# FK723MK1_ZGT6_Large.net
KiCad netlist of a schematic drawn in Altium Designer
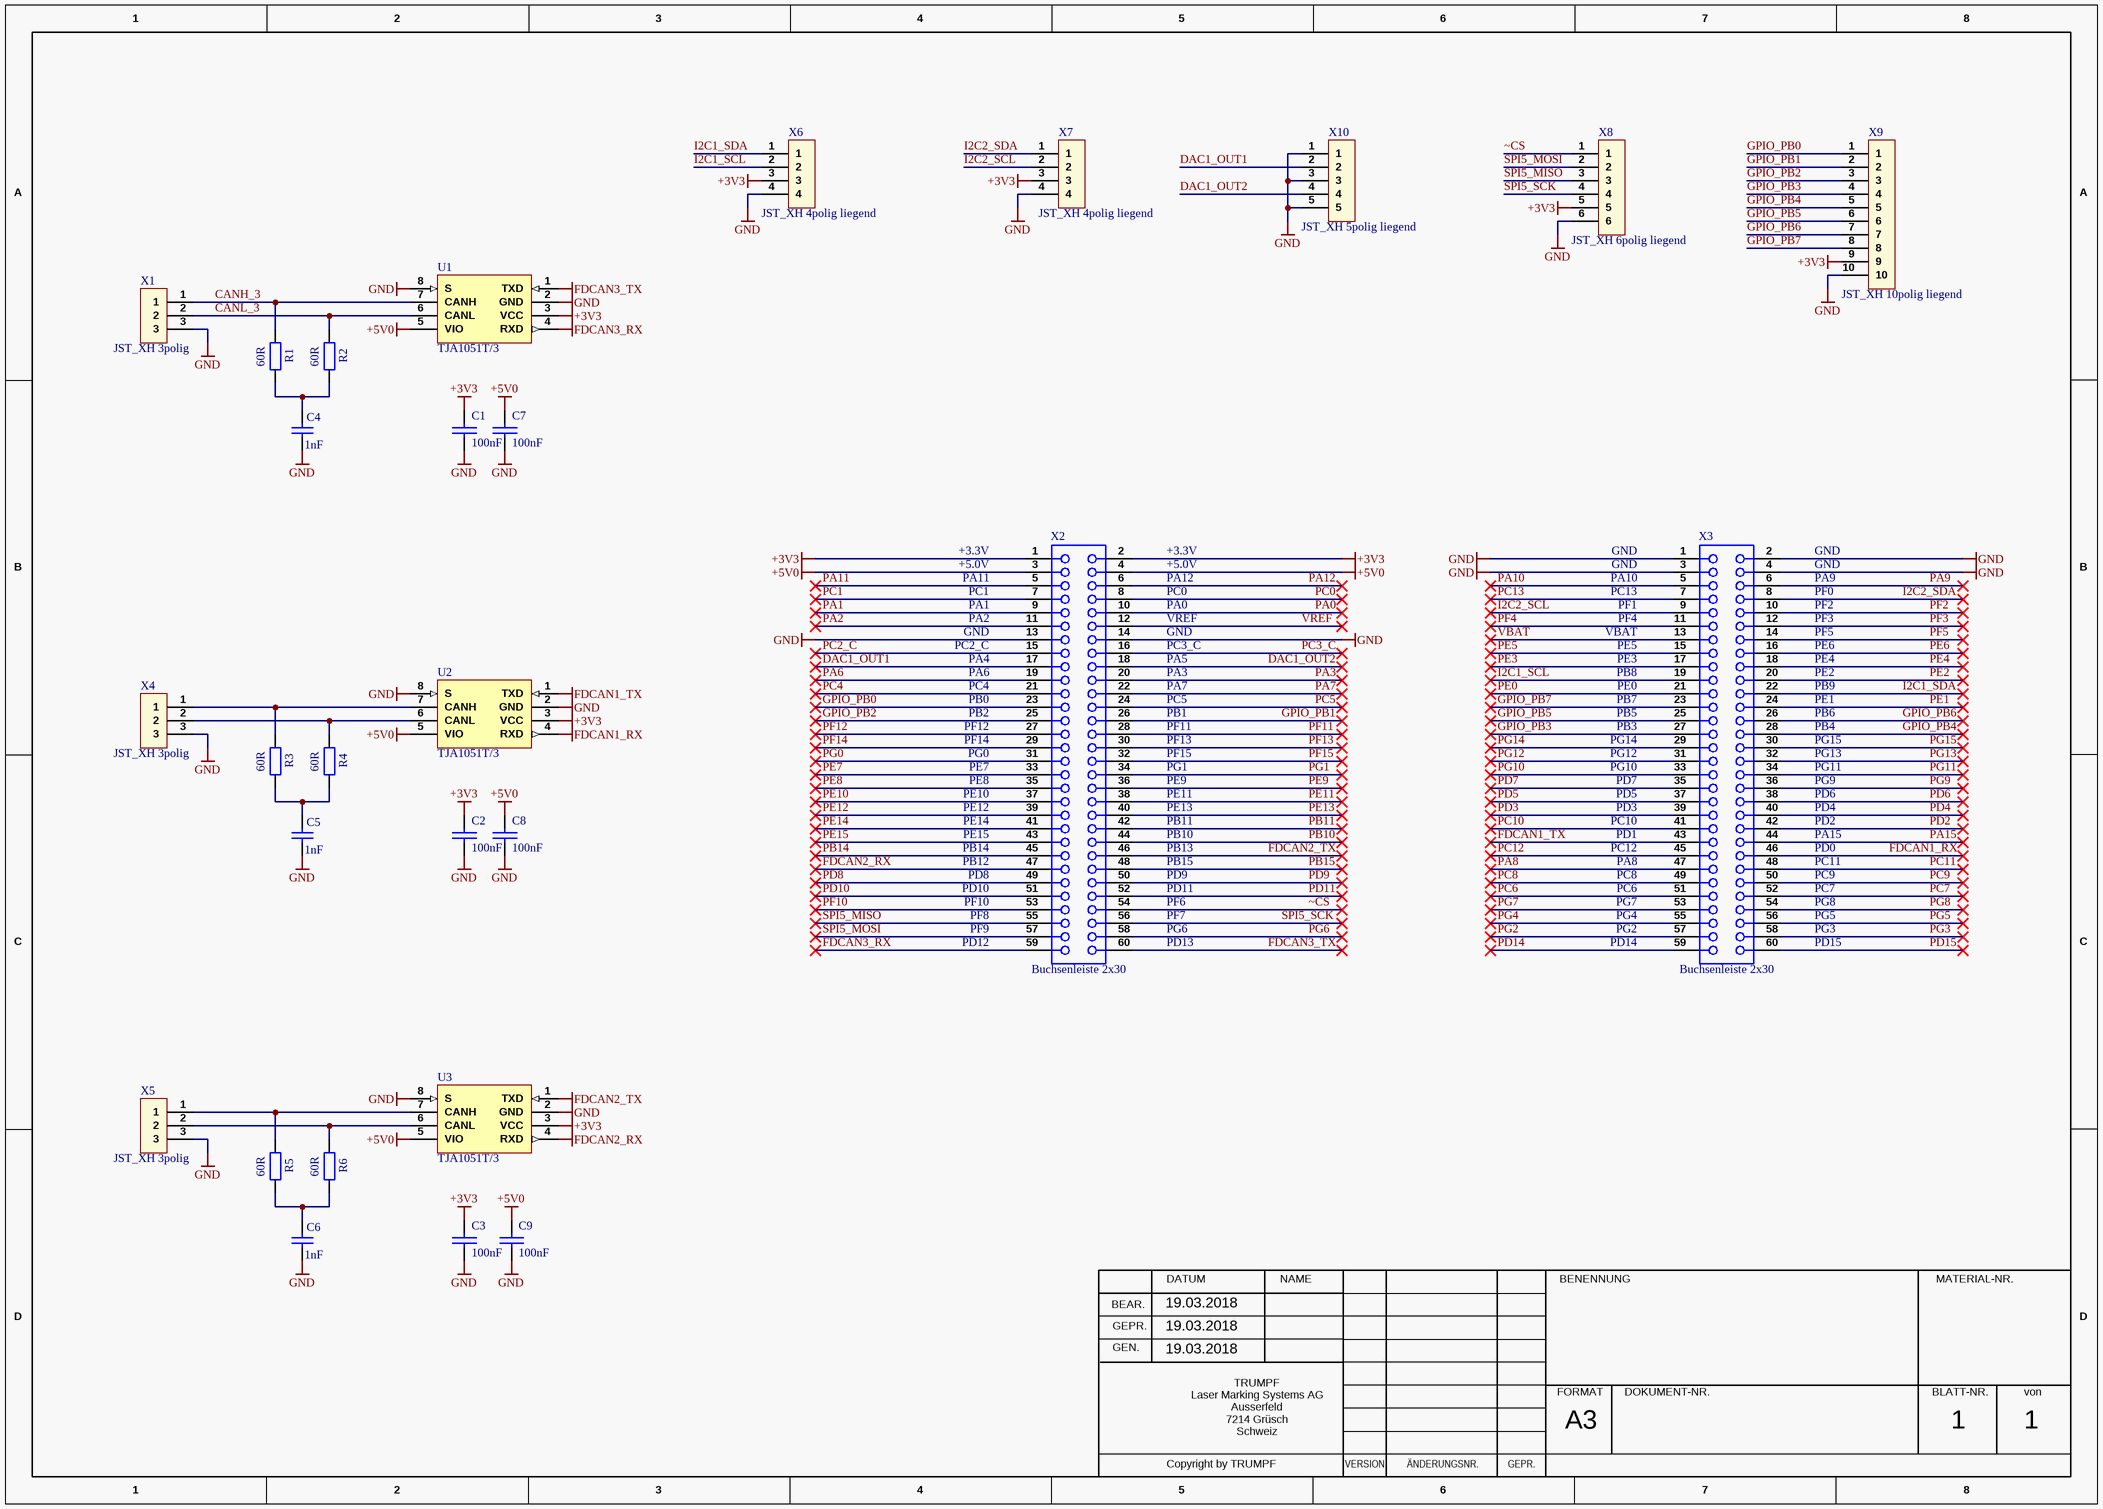
[diagram p0: FK723MK1_ZGT6_Large.SchDoc]

(export (version "E")
  (design (tool "Eeschema 10.0.6"))
  (components
    (comp (ref "C1")
      (value "100nF")
      (footprint "0402")
      (description "100nF 16V 10% 0402")
      (libsource (lib "ChipCapacitors") (part "100nF"))
    )
    (comp (ref "C2")
      (value "100nF")
      (footprint "0402")
      (description "100nF 16V 10% 0402")
      (libsource (lib "ChipCapacitors") (part "100nF"))
    )
    (comp (ref "C3")
      (value "100nF")
      (footprint "0402")
      (description "100nF 16V 10% 0402")
      (libsource (lib "ChipCapacitors") (part "100nF"))
    )
    (comp (ref "C4")
      (value "1nF")
      (footprint "WCAP-CSGP_0603_L1.6W0.8H0.8_Reflow")
      (description "WCAP-CSGP Multilayer Ceramic Chip Capacitor, General Purpose, size 0603, 1nF, 10V")
      (fields
        (field (name "MANUFACTURER PART NUMBER") "885012006014")
        (field (name "MANUFACTURER") "Wurth Elektronik")
      )
      (libsource (lib "Altium_WCAP-CSGP (rev25c)") (part "885012006014"))
    )
    (comp (ref "C5")
      (value "1nF")
      (footprint "WCAP-CSGP_0603_L1.6W0.8H0.8_Reflow")
      (description "WCAP-CSGP Multilayer Ceramic Chip Capacitor, General Purpose, size 0603, 1nF, 10V")
      (fields
        (field (name "MANUFACTURER PART NUMBER") "885012006014")
        (field (name "MANUFACTURER") "Wurth Elektronik")
      )
      (libsource (lib "Altium_WCAP-CSGP (rev25c)") (part "885012006014"))
    )
    (comp (ref "C6")
      (value "1nF")
      (footprint "WCAP-CSGP_0603_L1.6W0.8H0.8_Reflow")
      (description "WCAP-CSGP Multilayer Ceramic Chip Capacitor, General Purpose, size 0603, 1nF, 10V")
      (fields
        (field (name "MANUFACTURER PART NUMBER") "885012006014")
        (field (name "MANUFACTURER") "Wurth Elektronik")
      )
      (libsource (lib "Altium_WCAP-CSGP (rev25c)") (part "885012006014"))
    )
    (comp (ref "C7")
      (value "100nF")
      (footprint "0402")
      (description "100nF 16V 10% 0402")
      (libsource (lib "ChipCapacitors") (part "100nF"))
    )
    (comp (ref "C8")
      (value "100nF")
      (footprint "0402")
      (description "100nF 16V 10% 0402")
      (libsource (lib "ChipCapacitors") (part "100nF"))
    )
    (comp (ref "C9")
      (value "100nF")
      (footprint "0402")
      (description "100nF 16V 10% 0402")
      (libsource (lib "ChipCapacitors") (part "100nF"))
    )
    (comp (ref "R1")
      (value "60R")
      (footprint "WRIS-KSKE_0805")
      (description "WRIS-KSKE Thick Film Resistor, SMT, size 0805, 0.1Ω, 0.33W, +/-1%")
      (fields
        (field (name "MANUFACTURER PART NUMBER") "560050320001")
        (field (name "MANUFACTURER") "Wurth Elektronik")
      )
      (libsource (lib "Altium_WRIS-KSKE (rev25b)") (part "560050320001"))
    )
    (comp (ref "R2")
      (value "60R")
      (footprint "WRIS-KSKE_0805")
      (description "WRIS-KSKE Thick Film Resistor, SMT, size 0805, 0.1Ω, 0.33W, +/-1%")
      (fields
        (field (name "MANUFACTURER PART NUMBER") "560050320001")
        (field (name "MANUFACTURER") "Wurth Elektronik")
      )
      (libsource (lib "Altium_WRIS-KSKE (rev25b)") (part "560050320001"))
    )
    (comp (ref "R3")
      (value "60R")
      (footprint "WRIS-KSKE_0805")
      (description "WRIS-KSKE Thick Film Resistor, SMT, size 0805, 0.1Ω, 0.33W, +/-1%")
      (fields
        (field (name "MANUFACTURER PART NUMBER") "560050320001")
        (field (name "MANUFACTURER") "Wurth Elektronik")
      )
      (libsource (lib "Altium_WRIS-KSKE (rev25b)") (part "560050320001"))
    )
    (comp (ref "R4")
      (value "60R")
      (footprint "WRIS-KSKE_0805")
      (description "WRIS-KSKE Thick Film Resistor, SMT, size 0805, 0.1Ω, 0.33W, +/-1%")
      (fields
        (field (name "MANUFACTURER PART NUMBER") "560050320001")
        (field (name "MANUFACTURER") "Wurth Elektronik")
      )
      (libsource (lib "Altium_WRIS-KSKE (rev25b)") (part "560050320001"))
    )
    (comp (ref "R5")
      (value "60R")
      (footprint "WRIS-KSKE_0805")
      (description "WRIS-KSKE Thick Film Resistor, SMT, size 0805, 0.1Ω, 0.33W, +/-1%")
      (fields
        (field (name "MANUFACTURER PART NUMBER") "560050320001")
        (field (name "MANUFACTURER") "Wurth Elektronik")
      )
      (libsource (lib "Altium_WRIS-KSKE (rev25b)") (part "560050320001"))
    )
    (comp (ref "R6")
      (value "60R")
      (footprint "WRIS-KSKE_0805")
      (description "WRIS-KSKE Thick Film Resistor, SMT, size 0805, 0.1Ω, 0.33W, +/-1%")
      (fields
        (field (name "MANUFACTURER PART NUMBER") "560050320001")
        (field (name "MANUFACTURER") "Wurth Elektronik")
      )
      (libsource (lib "Altium_WRIS-KSKE (rev25b)") (part "560050320001"))
    )
    (comp (ref "U1") (value "TJA1051T/3") (footprint "SO-8") (libsource (lib "TJA1051") (part "TJA1051T/3")))
    (comp (ref "U2") (value "TJA1051T/3") (footprint "SO-8") (libsource (lib "TJA1051") (part "TJA1051T/3")))
    (comp (ref "U3") (value "TJA1051T/3") (footprint "SO-8") (libsource (lib "TJA1051") (part "TJA1051T/3")))
    (comp (ref "X1")
      (value "JST_XH 3polig")
      (footprint "JST_XH 3polig, liegend")
      (libsource (lib "JST_XH") (part "JST_XH 3polig"))
    )
    (comp (ref "X2")
      (value "Buchsenleiste 2x30")
      (footprint "Buchsenleiste 2x30polig")
      (libsource (lib "Buchsenleiste60polig") (part "Buchsenleiste 2x30"))
    )
    (comp (ref "X3")
      (value "Buchsenleiste 2x30")
      (footprint "Buchsenleiste 2x30polig")
      (libsource (lib "Buchsenleiste60polig") (part "Buchsenleiste 2x30"))
    )
    (comp (ref "X4")
      (value "JST_XH 3polig")
      (footprint "JST_XH 3polig, liegend")
      (libsource (lib "JST_XH") (part "JST_XH 3polig"))
    )
    (comp (ref "X5")
      (value "JST_XH 3polig")
      (footprint "JST_XH 3polig, liegend")
      (libsource (lib "JST_XH") (part "JST_XH 3polig"))
    )
    (comp (ref "X6")
      (value "JST_XH 4polig liegend")
      (footprint "JST_XH 4polig, liegend")
      (libsource (lib "JST_XH") (part "JST_XH 4polig"))
    )
    (comp (ref "X7")
      (value "JST_XH 4polig liegend")
      (footprint "JST_XH 4polig, liegend")
      (libsource (lib "JST_XH") (part "JST_XH 4polig"))
    )
    (comp (ref "X8")
      (value "JST_XH 6polig liegend")
      (footprint "JST_XH 6polig, liegend")
      (libsource (lib "JST_XH") (part "JST_XH 6polig"))
    )
    (comp (ref "X9")
      (value "JST_XH 10polig liegend")
      (footprint "JST_XH 10polig, liegend")
      (libsource (lib "JST_XH") (part "JST_XH 10polig"))
    )
    (comp (ref "X10")
      (value "JST_XH 5polig liegend")
      (footprint "JST_XH 5polig, liegend")
      (libsource (lib "JST_XH") (part "JST_XH 5polig"))
    )
  )
  (nets
    (net (code "1") (name "+3V3") (class "Default")
      (node (ref "C1") (pin "1") (pinfunction "1_1") (pintype "passive"))
      (node (ref "C2") (pin "1") (pinfunction "1_1") (pintype "passive"))
      (node (ref "C3") (pin "1") (pinfunction "1_1") (pintype "passive"))
      (node (ref "U1") (pin "3") (pinfunction "VCC_3") (pintype "power_in"))
      (node (ref "U2") (pin "3") (pinfunction "VCC_3") (pintype "power_in"))
      (node (ref "U3") (pin "3") (pinfunction "VCC_3") (pintype "power_in"))
      (node (ref "X2") (pin "1") (pinfunction "1_1") (pintype "passive"))
      (node (ref "X2") (pin "2") (pinfunction "2_2") (pintype "passive"))
      (node (ref "X6") (pin "3") (pinfunction "3_3") (pintype "passive"))
      (node (ref "X7") (pin "3") (pinfunction "3_3") (pintype "passive"))
      (node (ref "X8") (pin "5") (pinfunction "5_5") (pintype "passive"))
      (node (ref "X9") (pin "9") (pinfunction "9_9") (pintype "passive"))
    )
    (net (code "2") (name "+5V0") (class "Default")
      (node (ref "C7") (pin "1") (pinfunction "1_1") (pintype "passive"))
      (node (ref "C8") (pin "1") (pinfunction "1_1") (pintype "passive"))
      (node (ref "C9") (pin "1") (pinfunction "1_1") (pintype "passive"))
      (node (ref "U1") (pin "5") (pinfunction "VIO_5") (pintype "power_in"))
      (node (ref "U2") (pin "5") (pinfunction "VIO_5") (pintype "power_in"))
      (node (ref "U3") (pin "5") (pinfunction "VIO_5") (pintype "power_in"))
      (node (ref "X2") (pin "3") (pinfunction "3_3") (pintype "passive"))
      (node (ref "X2") (pin "4") (pinfunction "4_4") (pintype "passive"))
    )
    (net (code "3") (name "/CANH_3") (class "Default")
      (node (ref "R1") (pin "2") (pinfunction "2_2") (pintype "passive"))
      (node (ref "U1") (pin "7") (pinfunction "CANH_7") (pintype "passive"))
      (node (ref "X1") (pin "1") (pinfunction "1_1") (pintype "passive"))
    )
    (net (code "4") (name "/CANL_3") (class "Default")
      (node (ref "R2") (pin "2") (pinfunction "2_2") (pintype "passive"))
      (node (ref "U1") (pin "6") (pinfunction "CANL_6") (pintype "passive"))
      (node (ref "X1") (pin "2") (pinfunction "2_2") (pintype "passive"))
    )
    (net (code "5") (name "/DAC1_OUT1") (class "Default")
      (node (ref "X10") (pin "2") (pinfunction "2_2") (pintype "passive"))
      (node (ref "X2") (pin "17") (pinfunction "17_17") (pintype "passive"))
    )
    (net (code "6") (name "/DAC1_OUT2") (class "Default")
      (node (ref "X10") (pin "4") (pinfunction "4_4") (pintype "passive"))
      (node (ref "X2") (pin "18") (pinfunction "18_18") (pintype "passive"))
    )
    (net (code "7") (name "/GPIO_PB0") (class "Default")
      (node (ref "X2") (pin "23") (pinfunction "23_23") (pintype "passive"))
      (node (ref "X9") (pin "1") (pinfunction "1_1") (pintype "passive"))
    )
    (net (code "8") (name "/GPIO_PB1") (class "Default")
      (node (ref "X2") (pin "26") (pinfunction "26_26") (pintype "passive"))
      (node (ref "X9") (pin "2") (pinfunction "2_2") (pintype "passive"))
    )
    (net (code "9") (name "/GPIO_PB2") (class "Default")
      (node (ref "X2") (pin "25") (pinfunction "25_25") (pintype "passive"))
      (node (ref "X9") (pin "3") (pinfunction "3_3") (pintype "passive"))
    )
    (net (code "10") (name "/GPIO_PB3") (class "Default")
      (node (ref "X3") (pin "27") (pinfunction "27_27") (pintype "passive"))
      (node (ref "X9") (pin "4") (pinfunction "4_4") (pintype "passive"))
    )
    (net (code "11") (name "/GPIO_PB4") (class "Default")
      (node (ref "X3") (pin "28") (pinfunction "28_28") (pintype "passive"))
      (node (ref "X9") (pin "5") (pinfunction "5_5") (pintype "passive"))
    )
    (net (code "12") (name "/GPIO_PB5") (class "Default")
      (node (ref "X3") (pin "25") (pinfunction "25_25") (pintype "passive"))
      (node (ref "X9") (pin "6") (pinfunction "6_6") (pintype "passive"))
    )
    (net (code "13") (name "/GPIO_PB6") (class "Default")
      (node (ref "X3") (pin "26") (pinfunction "26_26") (pintype "passive"))
      (node (ref "X9") (pin "7") (pinfunction "7_7") (pintype "passive"))
    )
    (net (code "14") (name "/GPIO_PB7") (class "Default")
      (node (ref "X3") (pin "23") (pinfunction "23_23") (pintype "passive"))
      (node (ref "X9") (pin "8") (pinfunction "8_8") (pintype "passive"))
    )
    (net (code "15") (name "/I2C1_SCL") (class "Default")
      (node (ref "X3") (pin "19") (pinfunction "19_19") (pintype "passive"))
      (node (ref "X6") (pin "2") (pinfunction "2_2") (pintype "passive"))
    )
    (net (code "16") (name "/I2C1_SDA") (class "Default")
      (node (ref "X3") (pin "22") (pinfunction "22_22") (pintype "passive"))
      (node (ref "X6") (pin "1") (pinfunction "1_1") (pintype "passive"))
    )
    (net (code "17") (name "/I2C2_SCL") (class "Default")
      (node (ref "X3") (pin "9") (pinfunction "9_9") (pintype "passive"))
      (node (ref "X7") (pin "2") (pinfunction "2_2") (pintype "passive"))
    )
    (net (code "18") (name "/I2C2_SDA") (class "Default")
      (node (ref "X3") (pin "8") (pinfunction "8_8") (pintype "passive"))
      (node (ref "X7") (pin "1") (pinfunction "1_1") (pintype "passive"))
    )
    (net (code "19") (name "/PA0") (class "Default")
      (node (ref "X2") (pin "10") (pinfunction "10_10") (pintype "passive+no_connect"))
    )
    (net (code "20") (name "/PA1") (class "Default")
      (node (ref "X2") (pin "9") (pinfunction "9_9") (pintype "passive+no_connect"))
    )
    (net (code "21") (name "/PA2") (class "Default")
      (node (ref "X2") (pin "11") (pinfunction "11_11") (pintype "passive+no_connect"))
    )
    (net (code "22") (name "/PA3") (class "Default")
      (node (ref "X2") (pin "20") (pinfunction "20_20") (pintype "passive+no_connect"))
    )
    (net (code "23") (name "/PA6") (class "Default")
      (node (ref "X2") (pin "19") (pinfunction "19_19") (pintype "passive+no_connect"))
    )
    (net (code "24") (name "/PA7") (class "Default")
      (node (ref "X2") (pin "22") (pinfunction "22_22") (pintype "passive+no_connect"))
    )
    (net (code "25") (name "/PA8") (class "Default")
      (node (ref "X3") (pin "47") (pinfunction "47_47") (pintype "passive+no_connect"))
    )
    (net (code "26") (name "/PA9") (class "Default")
      (node (ref "X3") (pin "6") (pinfunction "6_6") (pintype "passive+no_connect"))
    )
    (net (code "27") (name "/PA10") (class "Default")
      (node (ref "X3") (pin "5") (pinfunction "5_5") (pintype "passive+no_connect"))
    )
    (net (code "28") (name "/PA11") (class "Default")
      (node (ref "X2") (pin "5") (pinfunction "5_5") (pintype "passive+no_connect"))
    )
    (net (code "29") (name "/PA12") (class "Default")
      (node (ref "X2") (pin "6") (pinfunction "6_6") (pintype "passive+no_connect"))
    )
    (net (code "30") (name "/PA15") (class "Default")
      (node (ref "X3") (pin "44") (pinfunction "44_44") (pintype "passive+no_connect"))
    )
    (net (code "31") (name "/PB10") (class "Default")
      (node (ref "X2") (pin "44") (pinfunction "44_44") (pintype "passive+no_connect"))
    )
    (net (code "32") (name "/PB11") (class "Default")
      (node (ref "X2") (pin "42") (pinfunction "42_42") (pintype "passive+no_connect"))
    )
    (net (code "33") (name "/PB14") (class "Default")
      (node (ref "X2") (pin "45") (pinfunction "45_45") (pintype "passive+no_connect"))
    )
    (net (code "34") (name "/PB15") (class "Default")
      (node (ref "X2") (pin "48") (pinfunction "48_48") (pintype "passive+no_connect"))
    )
    (net (code "35") (name "/PC0") (class "Default")
      (node (ref "X2") (pin "8") (pinfunction "8_8") (pintype "passive+no_connect"))
    )
    (net (code "36") (name "/PC1") (class "Default")
      (node (ref "X2") (pin "7") (pinfunction "7_7") (pintype "passive+no_connect"))
    )
    (net (code "37") (name "/PC2_C") (class "Default")
      (node (ref "X2") (pin "15") (pinfunction "15_15") (pintype "passive+no_connect"))
    )
    (net (code "38") (name "/PC3_C") (class "Default")
      (node (ref "X2") (pin "16") (pinfunction "16_16") (pintype "passive+no_connect"))
    )
    (net (code "39") (name "/PC4") (class "Default")
      (node (ref "X2") (pin "21") (pinfunction "21_21") (pintype "passive+no_connect"))
    )
    (net (code "40") (name "/PC5") (class "Default")
      (node (ref "X2") (pin "24") (pinfunction "24_24") (pintype "passive+no_connect"))
    )
    (net (code "41") (name "/PC6") (class "Default")
      (node (ref "X3") (pin "51") (pinfunction "51_51") (pintype "passive+no_connect"))
    )
    (net (code "42") (name "/PC7") (class "Default")
      (node (ref "X3") (pin "52") (pinfunction "52_52") (pintype "passive+no_connect"))
    )
    (net (code "43") (name "/PC8") (class "Default")
      (node (ref "X3") (pin "49") (pinfunction "49_49") (pintype "passive+no_connect"))
    )
    (net (code "44") (name "/PC9") (class "Default")
      (node (ref "X3") (pin "50") (pinfunction "50_50") (pintype "passive+no_connect"))
    )
    (net (code "45") (name "/PC10") (class "Default")
      (node (ref "X3") (pin "41") (pinfunction "41_41") (pintype "passive+no_connect"))
    )
    (net (code "46") (name "/PC11") (class "Default")
      (node (ref "X3") (pin "48") (pinfunction "48_48") (pintype "passive+no_connect"))
    )
    (net (code "47") (name "/PC12") (class "Default")
      (node (ref "X3") (pin "45") (pinfunction "45_45") (pintype "passive+no_connect"))
    )
    (net (code "48") (name "/PC13") (class "Default")
      (node (ref "X3") (pin "7") (pinfunction "7_7") (pintype "passive+no_connect"))
    )
    (net (code "49") (name "/PD2") (class "Default")
      (node (ref "X3") (pin "42") (pinfunction "42_42") (pintype "passive+no_connect"))
    )
    (net (code "50") (name "/PD3") (class "Default")
      (node (ref "X3") (pin "39") (pinfunction "39_39") (pintype "passive+no_connect"))
    )
    (net (code "51") (name "/PD4") (class "Default")
      (node (ref "X3") (pin "40") (pinfunction "40_40") (pintype "passive+no_connect"))
    )
    (net (code "52") (name "/PD5") (class "Default")
      (node (ref "X3") (pin "37") (pinfunction "37_37") (pintype "passive+no_connect"))
    )
    (net (code "53") (name "/PD6") (class "Default")
      (node (ref "X3") (pin "38") (pinfunction "38_38") (pintype "passive+no_connect"))
    )
    (net (code "54") (name "/PD7") (class "Default")
      (node (ref "X3") (pin "35") (pinfunction "35_35") (pintype "passive+no_connect"))
    )
    (net (code "55") (name "/PD8") (class "Default")
      (node (ref "X2") (pin "49") (pinfunction "49_49") (pintype "passive+no_connect"))
    )
    (net (code "56") (name "/PD9") (class "Default")
      (node (ref "X2") (pin "50") (pinfunction "50_50") (pintype "passive+no_connect"))
    )
    (net (code "57") (name "/PD10") (class "Default")
      (node (ref "X2") (pin "51") (pinfunction "51_51") (pintype "passive+no_connect"))
    )
    (net (code "58") (name "/PD11") (class "Default")
      (node (ref "X2") (pin "52") (pinfunction "52_52") (pintype "passive+no_connect"))
    )
    (net (code "59") (name "/PD14") (class "Default")
      (node (ref "X3") (pin "59") (pinfunction "59_59") (pintype "passive+no_connect"))
    )
    (net (code "60") (name "/PD15") (class "Default")
      (node (ref "X3") (pin "60") (pinfunction "60_60") (pintype "passive+no_connect"))
    )
    (net (code "61") (name "/PE0") (class "Default")
      (node (ref "X3") (pin "21") (pinfunction "21_21") (pintype "passive+no_connect"))
    )
    (net (code "62") (name "/PE1") (class "Default")
      (node (ref "X3") (pin "24") (pinfunction "24_24") (pintype "passive+no_connect"))
    )
    (net (code "63") (name "/PE2") (class "Default")
      (node (ref "X3") (pin "20") (pinfunction "20_20") (pintype "passive+no_connect"))
    )
    (net (code "64") (name "/PE3") (class "Default")
      (node (ref "X3") (pin "17") (pinfunction "17_17") (pintype "passive+no_connect"))
    )
    (net (code "65") (name "/PE4") (class "Default")
      (node (ref "X3") (pin "18") (pinfunction "18_18") (pintype "passive+no_connect"))
    )
    (net (code "66") (name "/PE5") (class "Default")
      (node (ref "X3") (pin "15") (pinfunction "15_15") (pintype "passive+no_connect"))
    )
    (net (code "67") (name "/PE6") (class "Default")
      (node (ref "X3") (pin "16") (pinfunction "16_16") (pintype "passive+no_connect"))
    )
    (net (code "68") (name "/PE7") (class "Default")
      (node (ref "X2") (pin "33") (pinfunction "33_33") (pintype "passive+no_connect"))
    )
    (net (code "69") (name "/PE8") (class "Default")
      (node (ref "X2") (pin "35") (pinfunction "35_35") (pintype "passive+no_connect"))
    )
    (net (code "70") (name "/PE9") (class "Default")
      (node (ref "X2") (pin "36") (pinfunction "36_36") (pintype "passive+no_connect"))
    )
    (net (code "71") (name "/PE10") (class "Default")
      (node (ref "X2") (pin "37") (pinfunction "37_37") (pintype "passive+no_connect"))
    )
    (net (code "72") (name "/PE11") (class "Default")
      (node (ref "X2") (pin "38") (pinfunction "38_38") (pintype "passive+no_connect"))
    )
    (net (code "73") (name "/PE12") (class "Default")
      (node (ref "X2") (pin "39") (pinfunction "39_39") (pintype "passive+no_connect"))
    )
    (net (code "74") (name "/PE13") (class "Default")
      (node (ref "X2") (pin "40") (pinfunction "40_40") (pintype "passive+no_connect"))
    )
    (net (code "75") (name "/PE14") (class "Default")
      (node (ref "X2") (pin "41") (pinfunction "41_41") (pintype "passive+no_connect"))
    )
    (net (code "76") (name "/PE15") (class "Default")
      (node (ref "X2") (pin "43") (pinfunction "43_43") (pintype "passive+no_connect"))
    )
    (net (code "77") (name "/PF2") (class "Default")
      (node (ref "X3") (pin "10") (pinfunction "10_10") (pintype "passive+no_connect"))
    )
    (net (code "78") (name "/PF3") (class "Default")
      (node (ref "X3") (pin "12") (pinfunction "12_12") (pintype "passive+no_connect"))
    )
    (net (code "79") (name "/PF4") (class "Default")
      (node (ref "X3") (pin "11") (pinfunction "11_11") (pintype "passive+no_connect"))
    )
    (net (code "80") (name "/PF5") (class "Default")
      (node (ref "X3") (pin "14") (pinfunction "14_14") (pintype "passive+no_connect"))
    )
    (net (code "81") (name "/PF10") (class "Default")
      (node (ref "X2") (pin "53") (pinfunction "53_53") (pintype "passive+no_connect"))
    )
    (net (code "82") (name "/PF11") (class "Default")
      (node (ref "X2") (pin "28") (pinfunction "28_28") (pintype "passive+no_connect"))
    )
    (net (code "83") (name "/PF12") (class "Default")
      (node (ref "X2") (pin "27") (pinfunction "27_27") (pintype "passive+no_connect"))
    )
    (net (code "84") (name "/PF13") (class "Default")
      (node (ref "X2") (pin "30") (pinfunction "30_30") (pintype "passive+no_connect"))
    )
    (net (code "85") (name "/PF14") (class "Default")
      (node (ref "X2") (pin "29") (pinfunction "29_29") (pintype "passive+no_connect"))
    )
    (net (code "86") (name "/PF15") (class "Default")
      (node (ref "X2") (pin "32") (pinfunction "32_32") (pintype "passive+no_connect"))
    )
    (net (code "87") (name "/PG0") (class "Default")
      (node (ref "X2") (pin "31") (pinfunction "31_31") (pintype "passive+no_connect"))
    )
    (net (code "88") (name "/PG1") (class "Default")
      (node (ref "X2") (pin "34") (pinfunction "34_34") (pintype "passive+no_connect"))
    )
    (net (code "89") (name "/PG2") (class "Default")
      (node (ref "X3") (pin "57") (pinfunction "57_57") (pintype "passive+no_connect"))
    )
    (net (code "90") (name "/PG3") (class "Default")
      (node (ref "X3") (pin "58") (pinfunction "58_58") (pintype "passive+no_connect"))
    )
    (net (code "91") (name "/PG4") (class "Default")
      (node (ref "X3") (pin "55") (pinfunction "55_55") (pintype "passive+no_connect"))
    )
    (net (code "92") (name "/PG5") (class "Default")
      (node (ref "X3") (pin "56") (pinfunction "56_56") (pintype "passive+no_connect"))
    )
    (net (code "93") (name "/PG6") (class "Default")
      (node (ref "X2") (pin "58") (pinfunction "58_58") (pintype "passive+no_connect"))
    )
    (net (code "94") (name "/PG7") (class "Default")
      (node (ref "X3") (pin "53") (pinfunction "53_53") (pintype "passive+no_connect"))
    )
    (net (code "95") (name "/PG8") (class "Default")
      (node (ref "X3") (pin "54") (pinfunction "54_54") (pintype "passive+no_connect"))
    )
    (net (code "96") (name "/PG9") (class "Default")
      (node (ref "X3") (pin "36") (pinfunction "36_36") (pintype "passive+no_connect"))
    )
    (net (code "97") (name "/PG10") (class "Default")
      (node (ref "X3") (pin "33") (pinfunction "33_33") (pintype "passive+no_connect"))
    )
    (net (code "98") (name "/PG11") (class "Default")
      (node (ref "X3") (pin "34") (pinfunction "34_34") (pintype "passive+no_connect"))
    )
    (net (code "99") (name "/PG12") (class "Default")
      (node (ref "X3") (pin "31") (pinfunction "31_31") (pintype "passive+no_connect"))
    )
    (net (code "100") (name "/PG13") (class "Default")
      (node (ref "X3") (pin "32") (pinfunction "32_32") (pintype "passive+no_connect"))
    )
    (net (code "101") (name "/PG14") (class "Default")
      (node (ref "X3") (pin "29") (pinfunction "29_29") (pintype "passive+no_connect"))
    )
    (net (code "102") (name "/PG15") (class "Default")
      (node (ref "X3") (pin "30") (pinfunction "30_30") (pintype "passive+no_connect"))
    )
    (net (code "103") (name "/SPI5_MISO") (class "Default")
      (node (ref "X2") (pin "55") (pinfunction "55_55") (pintype "passive"))
      (node (ref "X8") (pin "3") (pinfunction "3_3") (pintype "passive"))
    )
    (net (code "104") (name "/SPI5_MOSI") (class "Default")
      (node (ref "X2") (pin "57") (pinfunction "57_57") (pintype "passive"))
      (node (ref "X8") (pin "2") (pinfunction "2_2") (pintype "passive"))
    )
    (net (code "105") (name "/SPI5_SCK") (class "Default")
      (node (ref "X2") (pin "56") (pinfunction "56_56") (pintype "passive"))
      (node (ref "X8") (pin "4") (pinfunction "4_4") (pintype "passive"))
    )
    (net (code "106") (name "/VBAT") (class "Default")
      (node (ref "X3") (pin "13") (pinfunction "13_13") (pintype "passive+no_connect"))
    )
    (net (code "107") (name "/VREF") (class "Default")
      (node (ref "X2") (pin "12") (pinfunction "12_12") (pintype "passive+no_connect"))
    )
    (net (code "108") (name "/~CS") (class "Default")
      (node (ref "X2") (pin "54") (pinfunction "54_54") (pintype "passive"))
      (node (ref "X8") (pin "1") (pinfunction "1_1") (pintype "passive"))
    )
    (net (code "109") (name "FDCAN1_RX") (class "Default")
      (node (ref "U2") (pin "4") (pinfunction "RXD_4") (pintype "output"))
      (node (ref "X3") (pin "46") (pinfunction "46_46") (pintype "passive"))
    )
    (net (code "110") (name "FDCAN1_TX") (class "Default")
      (node (ref "U2") (pin "1") (pinfunction "TXD_1") (pintype "input"))
      (node (ref "X3") (pin "43") (pinfunction "43_43") (pintype "passive"))
    )
    (net (code "111") (name "FDCAN2_RX") (class "Default")
      (node (ref "U3") (pin "4") (pinfunction "RXD_4") (pintype "output"))
      (node (ref "X2") (pin "47") (pinfunction "47_47") (pintype "passive"))
    )
    (net (code "112") (name "FDCAN2_TX") (class "Default")
      (node (ref "U3") (pin "1") (pinfunction "TXD_1") (pintype "input"))
      (node (ref "X2") (pin "46") (pinfunction "46_46") (pintype "passive"))
    )
    (net (code "113") (name "FDCAN3_RX") (class "Default")
      (node (ref "U1") (pin "4") (pinfunction "RXD_4") (pintype "output"))
      (node (ref "X2") (pin "59") (pinfunction "59_59") (pintype "passive"))
    )
    (net (code "114") (name "FDCAN3_TX") (class "Default")
      (node (ref "U1") (pin "1") (pinfunction "TXD_1") (pintype "input"))
      (node (ref "X2") (pin "60") (pinfunction "60_60") (pintype "passive"))
    )
    (net (code "115") (name "GND") (class "Default")
      (node (ref "C1") (pin "2") (pinfunction "2_2") (pintype "passive"))
      (node (ref "C2") (pin "2") (pinfunction "2_2") (pintype "passive"))
      (node (ref "C3") (pin "2") (pinfunction "2_2") (pintype "passive"))
      (node (ref "C4") (pin "1") (pinfunction "1_1") (pintype "passive"))
      (node (ref "C5") (pin "1") (pinfunction "1_1") (pintype "passive"))
      (node (ref "C6") (pin "1") (pinfunction "1_1") (pintype "passive"))
      (node (ref "C7") (pin "2") (pinfunction "2_2") (pintype "passive"))
      (node (ref "C8") (pin "2") (pinfunction "2_2") (pintype "passive"))
      (node (ref "C9") (pin "2") (pinfunction "2_2") (pintype "passive"))
      (node (ref "U1") (pin "2") (pinfunction "GND_2") (pintype "power_in"))
      (node (ref "U1") (pin "8") (pinfunction "S_8") (pintype "input"))
      (node (ref "U2") (pin "2") (pinfunction "GND_2") (pintype "power_in"))
      (node (ref "U2") (pin "8") (pinfunction "S_8") (pintype "input"))
      (node (ref "U3") (pin "2") (pinfunction "GND_2") (pintype "power_in"))
      (node (ref "U3") (pin "8") (pinfunction "S_8") (pintype "input"))
      (node (ref "X1") (pin "3") (pinfunction "3_3") (pintype "passive"))
      (node (ref "X10") (pin "1") (pinfunction "1_1") (pintype "passive"))
      (node (ref "X10") (pin "3") (pinfunction "3_3") (pintype "passive"))
      (node (ref "X10") (pin "5") (pinfunction "5_5") (pintype "passive"))
      (node (ref "X2") (pin "13") (pinfunction "13_13") (pintype "passive"))
      (node (ref "X2") (pin "14") (pinfunction "14_14") (pintype "passive"))
      (node (ref "X3") (pin "1") (pinfunction "1_1") (pintype "passive"))
      (node (ref "X3") (pin "2") (pinfunction "2_2") (pintype "passive"))
      (node (ref "X3") (pin "3") (pinfunction "3_3") (pintype "passive"))
      (node (ref "X3") (pin "4") (pinfunction "4_4") (pintype "passive"))
      (node (ref "X4") (pin "3") (pinfunction "3_3") (pintype "passive"))
      (node (ref "X5") (pin "3") (pinfunction "3_3") (pintype "passive"))
      (node (ref "X6") (pin "4") (pinfunction "4_4") (pintype "passive"))
      (node (ref "X7") (pin "4") (pinfunction "4_4") (pintype "passive"))
      (node (ref "X8") (pin "6") (pinfunction "6_6") (pintype "passive"))
      (node (ref "X9") (pin "10") (pinfunction "10_10") (pintype "passive"))
    )
    (net (code "116") (name "Net-(C4-Pad2)") (class "Default")
      (node (ref "C4") (pin "2") (pinfunction "2_2") (pintype "passive"))
      (node (ref "R1") (pin "1") (pinfunction "1_1") (pintype "passive"))
      (node (ref "R2") (pin "1") (pinfunction "1_1") (pintype "passive"))
    )
    (net (code "117") (name "Net-(C5-Pad2)") (class "Default")
      (node (ref "C5") (pin "2") (pinfunction "2_2") (pintype "passive"))
      (node (ref "R3") (pin "1") (pinfunction "1_1") (pintype "passive"))
      (node (ref "R4") (pin "1") (pinfunction "1_1") (pintype "passive"))
    )
    (net (code "118") (name "Net-(C6-Pad2)") (class "Default")
      (node (ref "C6") (pin "2") (pinfunction "2_2") (pintype "passive"))
      (node (ref "R5") (pin "1") (pinfunction "1_1") (pintype "passive"))
      (node (ref "R6") (pin "1") (pinfunction "1_1") (pintype "passive"))
    )
    (net (code "119") (name "Net-(U2-CANH)") (class "Default")
      (node (ref "R3") (pin "2") (pinfunction "2_2") (pintype "passive"))
      (node (ref "U2") (pin "7") (pinfunction "CANH_7") (pintype "passive"))
      (node (ref "X4") (pin "1") (pinfunction "1_1") (pintype "passive"))
    )
    (net (code "120") (name "Net-(U2-CANL)") (class "Default")
      (node (ref "R4") (pin "2") (pinfunction "2_2") (pintype "passive"))
      (node (ref "U2") (pin "6") (pinfunction "CANL_6") (pintype "passive"))
      (node (ref "X4") (pin "2") (pinfunction "2_2") (pintype "passive"))
    )
    (net (code "121") (name "Net-(U3-CANH)") (class "Default")
      (node (ref "R5") (pin "2") (pinfunction "2_2") (pintype "passive"))
      (node (ref "U3") (pin "7") (pinfunction "CANH_7") (pintype "passive"))
      (node (ref "X5") (pin "1") (pinfunction "1_1") (pintype "passive"))
    )
    (net (code "122") (name "Net-(U3-CANL)") (class "Default")
      (node (ref "R6") (pin "2") (pinfunction "2_2") (pintype "passive"))
      (node (ref "U3") (pin "6") (pinfunction "CANL_6") (pintype "passive"))
      (node (ref "X5") (pin "2") (pinfunction "2_2") (pintype "passive"))
    )
  )
)
